# Voeding.net
KiCad netlist of a schematic drawn in Altium Designer
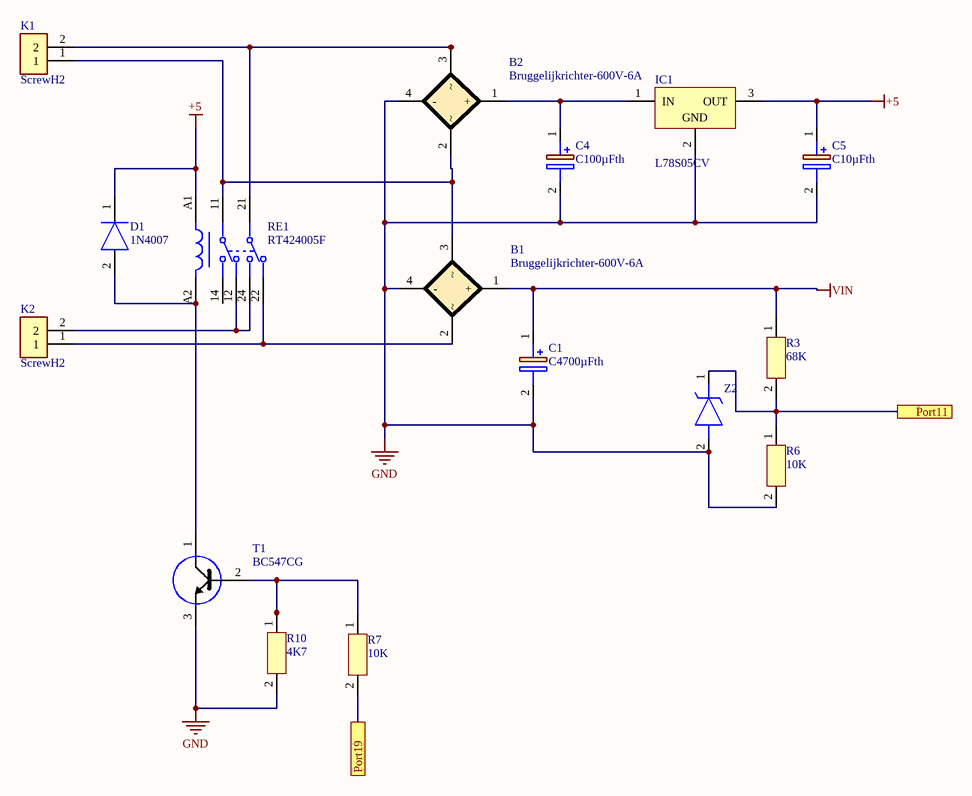
[diagram p0: Voeding.SchDoc]

(export (version "E")
  (design (tool "Eeschema 10.0.6"))
  (components
    (comp (ref "B1")
      (value "Bruggelijkrichter-600V-6A")
      (footprint "Bruggelijkrichter-600V-6A")
      (description "Bridge Rectifier")
      (fields (field (name "MANUFACTURER_PART_NUMBER") "GBU6J-E3/45"))
      (libsource (lib "Soldeerbout_12002498") (part "Bruggelijkrichter-600V-6A"))
    )
    (comp (ref "B2")
      (value "Bruggelijkrichter-600V-6A")
      (footprint "Bruggelijkrichter-600V-6A")
      (description "Bridge Rectifier")
      (fields (field (name "MANUFACTURER_PART_NUMBER") "GBU6J-E3/45"))
      (libsource (lib "Soldeerbout_12002498") (part "Bruggelijkrichter-600V-6A"))
    )
    (comp (ref "C1")
      (value "C4700µFth")
      (footprint "C4700µFth")
      (description "Capacitor Polarised")
      (fields
        (field (name "MOUSER2 PART NUMBER") "80-ESK478M050AQ3AA")
        (field (name "MANUFACTURER_PART_NUMBER") "ESK478M050AQ3AA")
      )
      (libsource (lib "Soldeerbout_12002498") (part "C4700µFth"))
    )
    (comp (ref "C4")
      (value "C100µFth")
      (footprint "C100µFth")
      (description "Capacitor Polarised")
      (fields (field (name "MANUFACTURER_PART_NUMBER") "ESK107M050AG3EA"))
      (libsource (lib "Soldeerbout_12002498") (part "C100µFth"))
    )
    (comp (ref "C5")
      (value "C10µFth")
      (footprint "C10µFth")
      (description "Capacitor Polarised")
      (fields
        (field (name "MOUSER2 PART NUMBER") "667-ECA-1HM100I")
        (field (name "MANUFACTURER_PART_NUMBER") "ECA-1HM100I")
      )
      (libsource (lib "Soldeerbout_12002498") (part "C10µFth"))
    )
    (comp (ref "D1")
      (value "1N4007")
      (footprint "1N4007")
      (description "Diode")
      (fields
        (field (name "MOUSER2 PART NUMBER") "583-1N4007-T")
        (field (name "MANUFACTURER_PART_NUMBER") "1N4007-T")
      )
      (libsource (lib "Soldeerbout_12002498") (part "1N4007"))
    )
    (comp (ref "IC1")
      (value "L78S05CV")
      (footprint "5V_Regulator-2A")
      (description "2A Positive Voltage Regulator, 5V, 3-Pin TO-220")
      (libsource (lib "Soldeerbout_12002498") (part "5V_Regulator-2A"))
    )
    (comp (ref "K1")
      (value "ScrewH2")
      (footprint "Soldeerbout_12002498:ScewH2")
      (description "Connector")
      (fields
        (field (name "MOUSER2 PART NUMBER") "490-TB007-508-02BE")
        (field (name "MANUFACTURER_PART_NUMBER") "TB007-508-02BE")
      )
      (libsource (lib "Soldeerbout_12002498") (part "ScrewH2"))
    )
    (comp (ref "K2")
      (value "ScrewH2")
      (footprint "Soldeerbout_12002498:ScewH2")
      (description "Connector")
      (fields
        (field (name "MOUSER2 PART NUMBER") "490-TB007-508-02BE")
        (field (name "MANUFACTURER_PART_NUMBER") "TB007-508-02BE")
      )
      (libsource (lib "Soldeerbout_12002498") (part "ScrewH2"))
    )
    (comp (ref "R3")
      (value "68K")
      (footprint "0805")
      (description "Resistor")
      (fields (field (name "MANUFACTURER_PART_NUMBER") "TNPU0805500RAZEN00"))
      (libsource (lib "Soldeerbout_12002498") (part "R-0805"))
    )
    (comp (ref "R6")
      (value "10K")
      (footprint "0805")
      (description "Resistor")
      (fields (field (name "MANUFACTURER_PART_NUMBER") "TNPU0805500RAZEN00"))
      (libsource (lib "Soldeerbout_12002498") (part "R-0805"))
    )
    (comp (ref "R7")
      (value "10K")
      (footprint "0805")
      (description "Resistor")
      (fields (field (name "MANUFACTURER_PART_NUMBER") "TNPU0805500RAZEN00"))
      (libsource (lib "Soldeerbout_12002498") (part "R-0805"))
    )
    (comp (ref "R10")
      (value "4K7")
      (footprint "0805")
      (description "Resistor")
      (fields (field (name "MANUFACTURER_PART_NUMBER") "TNPU0805500RAZEN00"))
      (libsource (lib "Soldeerbout_12002498") (part "R-0805"))
    )
    (comp (ref "RE1")
      (value "RT424005F")
      (footprint "vermogenrelais-5VDC-8A")
      (description "RELAY GENERAL PURPOSE DPDT 8A 5V")
      (libsource (lib "Soldeerbout_12002498") (part "vermogenrelais-5VDC-8A"))
    )
    (comp (ref "T1")
      (value "BC547CG")
      (footprint "BC547C")
      (description "Amplifier Transistor, NPN Silicon, 3-Pin TO-92, Pb-Free, Bulk Box")
      (fields (field (name "MANUFACTURER") "On Semiconductor"))
      (libsource (lib "Soldeerbout_12002498") (part "BC547C"))
    )
    (comp (ref "Z2")
      (value "zenerdiode-5,1V-0,5W")
      (footprint "Soldeerbout_12002498:zenerdiode-5,1V-0,5W")
      (description "Zener Diode")
      (fields (field (name "MANUFACTURER_PART_NUMBER") "MM5Z4689T1G"))
      (libsource (lib "Soldeerbout_12002498") (part "zenerdiode-5,1V-0,5W"))
    )
  )
  (nets
    (net (code "1") (name "+5") (class "Default")
      (node (ref "C5") (pin "1") (pinfunction "+_1") (pintype "passive"))
      (node (ref "D1") (pin "1") (pinfunction "K_1") (pintype "passive"))
      (node (ref "IC1") (pin "3") (pinfunction "OUT_3") (pintype "power_in"))
      (node (ref "RE1") (pin "A1") (pinfunction "A1_A1") (pintype "passive"))
    )
    (net (code "2") (name "/Port11") (class "Default")
      (node (ref "R3") (pin "2") (pinfunction "2_2") (pintype "passive"))
      (node (ref "R6") (pin "1") (pinfunction "1_1") (pintype "passive"))
      (node (ref "Z2") (pin "1") (pinfunction "K_1") (pintype "passive"))
    )
    (net (code "3") (name "/Port19") (class "Default")
      (node (ref "R7") (pin "2") (pinfunction "2_2") (pintype "passive"))
    )
    (net (code "4") (name "GND") (class "Default")
      (node (ref "B1") (pin "4") (pinfunction "-_4") (pintype "passive"))
      (node (ref "B2") (pin "4") (pinfunction "-_4") (pintype "passive"))
      (node (ref "C1") (pin "2") (pinfunction "-_2") (pintype "passive"))
      (node (ref "C4") (pin "2") (pinfunction "-_2") (pintype "passive"))
      (node (ref "C5") (pin "2") (pinfunction "-_2") (pintype "passive"))
      (node (ref "IC1") (pin "2") (pinfunction "GND_2") (pintype "power_in"))
      (node (ref "R10") (pin "2") (pinfunction "2_2") (pintype "passive"))
      (node (ref "R6") (pin "2") (pinfunction "2_2") (pintype "passive"))
      (node (ref "T1") (pin "3") (pinfunction "E_3") (pintype "passive"))
      (node (ref "Z2") (pin "2") (pinfunction "A_2") (pintype "passive"))
    )
    (net (code "5") (name "Net-(B1-~-Pad2)") (class "Default")
      (node (ref "B1") (pin "2") (pinfunction "~_2") (pintype "passive"))
      (node (ref "K2") (pin "1") (pinfunction "1_1") (pintype "passive"))
      (node (ref "RE1") (pin "22") (pinfunction "22_22") (pintype "passive"))
    )
    (net (code "6") (name "Net-(B1-~-Pad3)") (class "Default")
      (node (ref "B1") (pin "3") (pinfunction "~_3") (pintype "passive"))
      (node (ref "B2") (pin "2") (pinfunction "~_2") (pintype "passive"))
      (node (ref "K1") (pin "1") (pinfunction "1_1") (pintype "passive"))
      (node (ref "RE1") (pin "11") (pinfunction "11_11") (pintype "passive"))
    )
    (net (code "7") (name "Net-(B2-+)") (class "Default")
      (node (ref "B2") (pin "1") (pinfunction "+_1") (pintype "passive"))
      (node (ref "C4") (pin "1") (pinfunction "+_1") (pintype "passive"))
      (node (ref "IC1") (pin "1") (pinfunction "IN_1") (pintype "power_in"))
    )
    (net (code "8") (name "Net-(B2-~-Pad3)") (class "Default")
      (node (ref "B2") (pin "3") (pinfunction "~_3") (pintype "passive"))
      (node (ref "K1") (pin "2") (pinfunction "2_2") (pintype "passive"))
      (node (ref "RE1") (pin "21") (pinfunction "21_21") (pintype "passive"))
    )
    (net (code "9") (name "Net-(D1-A)") (class "Default")
      (node (ref "D1") (pin "2") (pinfunction "A_2") (pintype "passive"))
      (node (ref "RE1") (pin "A2") (pinfunction "A2_A2") (pintype "passive"))
      (node (ref "T1") (pin "1") (pinfunction "C_1") (pintype "passive"))
    )
    (net (code "10") (name "Net-(K2-Pad2)") (class "Default")
      (node (ref "K2") (pin "2") (pinfunction "2_2") (pintype "passive"))
      (node (ref "RE1") (pin "12") (pinfunction "12_12") (pintype "passive"))
      (node (ref "RE1") (pin "24") (pinfunction "24_24") (pintype "passive"))
    )
    (net (code "11") (name "Net-(T1-B)") (class "Default")
      (node (ref "R10") (pin "1") (pinfunction "1_1") (pintype "passive"))
      (node (ref "R7") (pin "1") (pinfunction "1_1") (pintype "passive"))
      (node (ref "T1") (pin "2") (pinfunction "B_2") (pintype "passive"))
    )
    (net (code "12") (name "VIN") (class "Default")
      (node (ref "B1") (pin "1") (pinfunction "+_1") (pintype "passive"))
      (node (ref "C1") (pin "1") (pinfunction "+_1") (pintype "passive"))
      (node (ref "R3") (pin "1") (pinfunction "1_1") (pintype "passive"))
    )
    (net (code "13") (name "unconnected-(RE1-Pad14)") (class "Default")
      (node (ref "RE1") (pin "14") (pinfunction "14_14") (pintype "passive"))
    )
  )
)
